# xmega1.net
KiCad netlist of a schematic drawn in EAGLE
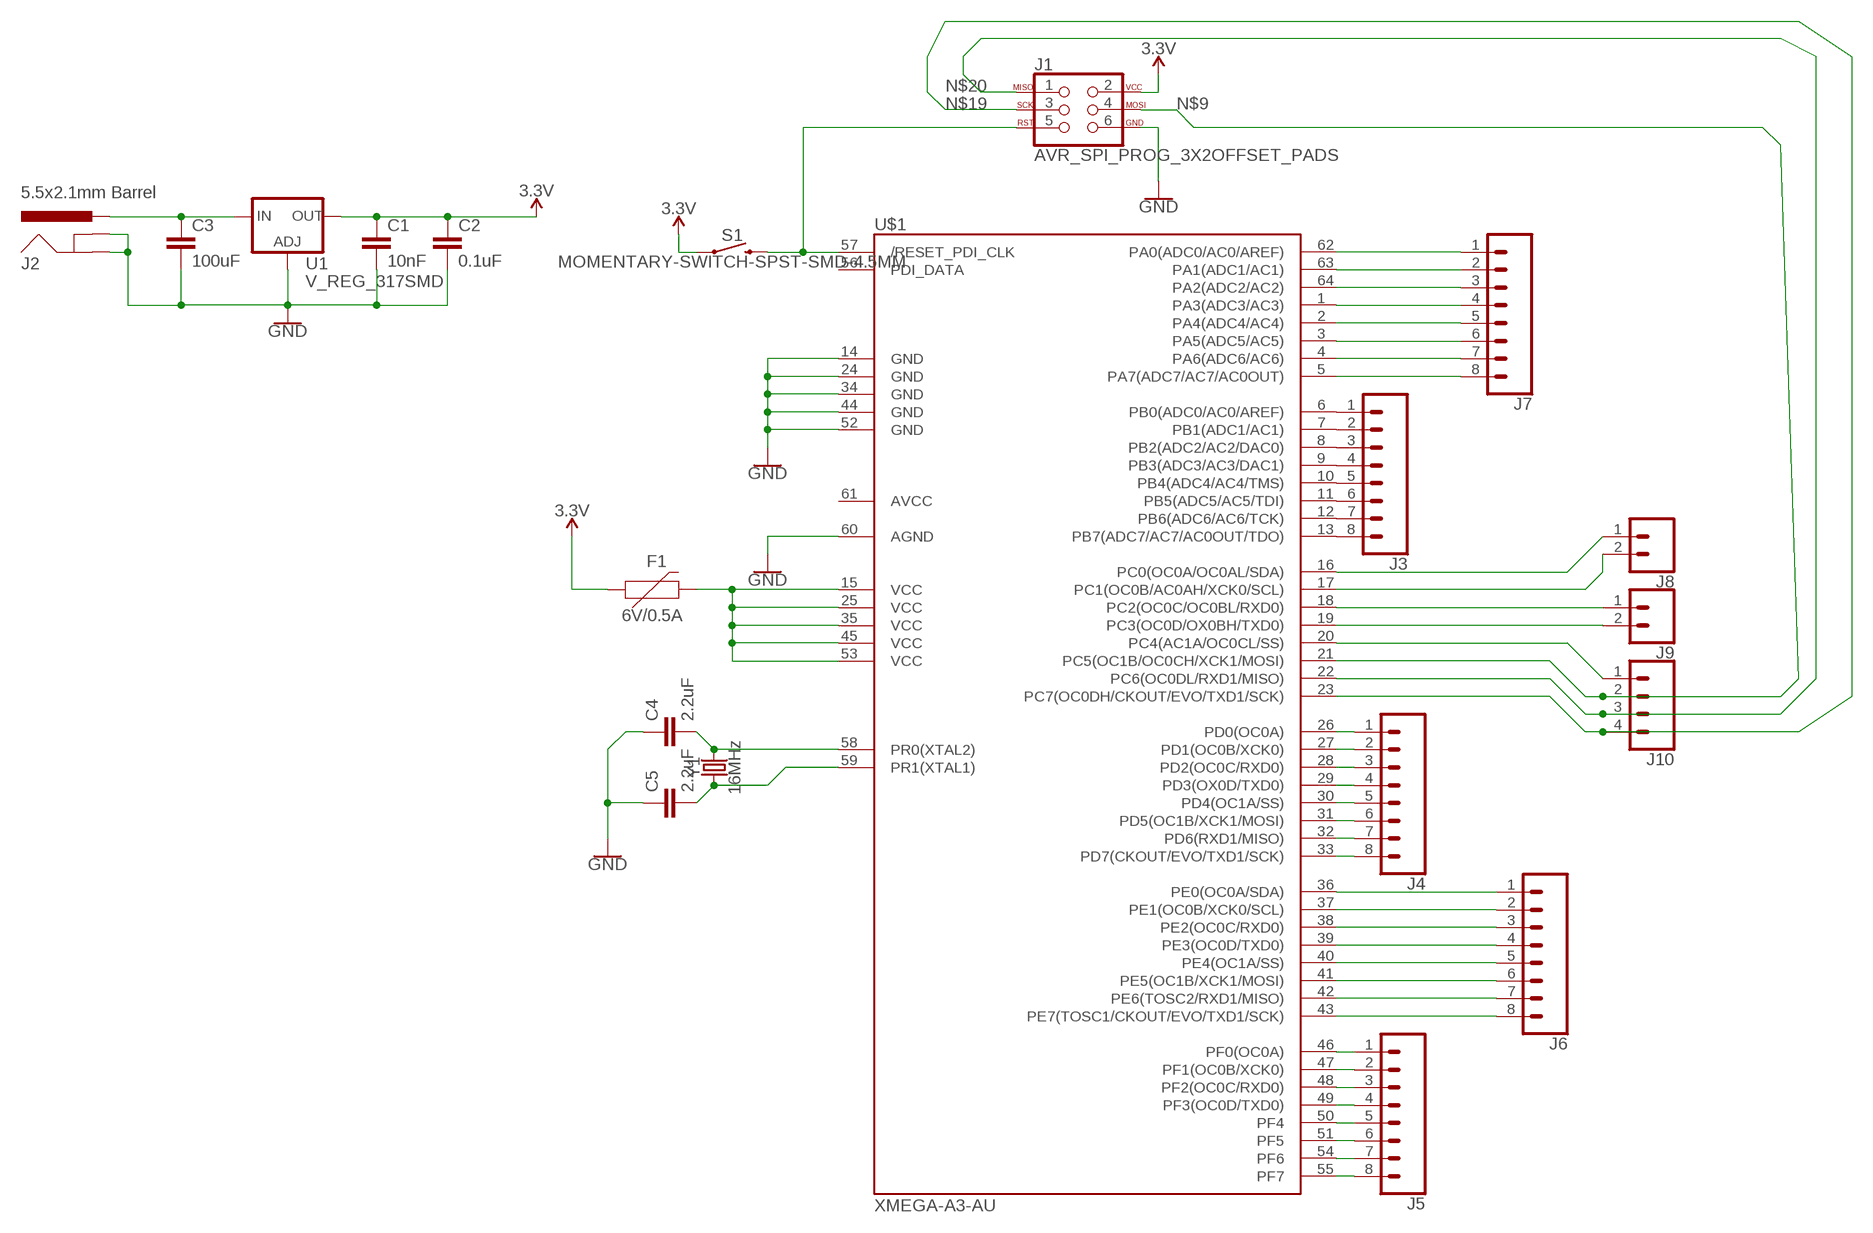
[diagram p0: schematic, sheet 1]

(export (version "E")
  (design (tool "Eeschema 10.0.6"))
  (components
    (comp (ref "C1")
      (value "10nF")
      (footprint "eagle-import:0603")
      (libsource (lib "eagle-import") (part "10NF-0603-50V-10%"))
    )
    (comp (ref "C2")
      (value "0.1uF")
      (footprint "eagle-import:0402-CAP")
      (libsource (lib "eagle-import") (part ".1UF-CER"))
    )
    (comp (ref "C3")
      (value "100uF")
      (footprint "eagle-import:1210")
      (libsource (lib "eagle-import") (part "100UF6.3V20%(1210)"))
    )
    (comp (ref "C4")
      (value "2.2uF")
      (footprint "eagle-import:0402-CAP")
      (libsource (lib "eagle-import") (part "2.2UF-CERCAP-07888"))
    )
    (comp (ref "C5")
      (value "2.2uF")
      (footprint "eagle-import:0402-CAP")
      (libsource (lib "eagle-import") (part "2.2UF-CERCAP-07888"))
    )
    (comp (ref "F1")
      (value "6V/0.5A")
      (footprint "eagle-import:1206")
      (libsource (lib "eagle-import") (part "PPTC_HALF-AMP"))
    )
    (comp (ref "J1")
      (value "AVR_SPI_PROG_3X2OFFSET_PADS")
      (footprint "eagle-import:2X3_OFFSET")
      (libsource (lib "eagle-import") (part "AVR_SPI_PROG_3X2OFFSET_PADS"))
    )
    (comp (ref "J2")
      (value "5.5x2.1mm Barrel")
      (footprint "eagle-import:POWER_JACK_SMD")
      (libsource (lib "eagle-import") (part "POWER_JACKSMD"))
    )
    (comp (ref "J3")
      (value "CONN_08LONGPADS")
      (footprint "eagle-import:1X08_LONGPADS")
      (libsource (lib "eagle-import") (part "CONN_08LONGPADS"))
    )
    (comp (ref "J4")
      (value "CONN_08LONGPADS")
      (footprint "eagle-import:1X08_LONGPADS")
      (libsource (lib "eagle-import") (part "CONN_08LONGPADS"))
    )
    (comp (ref "J5")
      (value "CONN_08LONGPADS")
      (footprint "eagle-import:1X08_LONGPADS")
      (libsource (lib "eagle-import") (part "CONN_08LONGPADS"))
    )
    (comp (ref "J6")
      (value "CONN_08LONGPADS")
      (footprint "eagle-import:1X08_LONGPADS")
      (libsource (lib "eagle-import") (part "CONN_08LONGPADS"))
    )
    (comp (ref "J7")
      (value "CONN_08LONGPADS")
      (footprint "eagle-import:1X08_LONGPADS")
      (libsource (lib "eagle-import") (part "CONN_08LONGPADS"))
    )
    (comp (ref "J8")
      (value "CONN_02PTH3")
      (footprint "eagle-import:1X02_LONGPADS")
      (libsource (lib "eagle-import") (part "CONN_02PTH3"))
    )
    (comp (ref "J9")
      (value "CONN_02PTH3")
      (footprint "eagle-import:1X02_LONGPADS")
      (libsource (lib "eagle-import") (part "CONN_02PTH3"))
    )
    (comp (ref "J10")
      (value "CONN_04LONGPADS")
      (footprint "eagle-import:1X04_LONGPADS")
      (libsource (lib "eagle-import") (part "CONN_04LONGPADS"))
    )
    (comp (ref "S1")
      (value "MOMENTARY-SWITCH-SPST-SMD-4.5MM")
      (footprint "eagle-import:TACTILE_SWITCH_SMD_4.5MM")
      (libsource (lib "eagle-import") (part "MOMENTARY-SWITCH-SPST-SMD-4.5MM"))
    )
    (comp (ref "U$1")
      (value "XMEGA-A3-AU")
      (footprint "eagle-import:TQFP64_14X14MM_MCU")
      (libsource (lib "eagle-import") (part "XMEGA-A3-AU"))
    )
    (comp (ref "U1")
      (value "V_REG_317SMD")
      (footprint "eagle-import:SOT223")
      (libsource (lib "eagle-import") (part "V_REG_317SMD"))
    )
    (comp (ref "Y1")
      (value "16MHz")
      (footprint "eagle-import:CRYSTAL-SMD-5X3.2-4PAD")
      (libsource (lib "eagle-import") (part "CRYSTAL-16MHZSMD-5X3.2"))
    )
  )
  (nets
    (net (code "1") (name "/N$9") (class "Default")
      (node (ref "J1") (pin "4") (pinfunction "4_4") (pintype "passive"))
      (node (ref "J10") (pin "2") (pinfunction "2_2") (pintype "passive"))
      (node (ref "U$1") (pin "21") (pinfunction "PC5(OC1B/OC0CH/XCK1/MOSI)_21") (pintype "bidirectional"))
    )
    (net (code "2") (name "/N$19") (class "Default")
      (node (ref "J1") (pin "3") (pinfunction "3_3") (pintype "passive"))
      (node (ref "J10") (pin "4") (pinfunction "4_4") (pintype "passive"))
      (node (ref "U$1") (pin "23") (pinfunction "PC7(OC0DH/CKOUT/EVO/TXD1/SCK)_23") (pintype "bidirectional"))
    )
    (net (code "3") (name "/N$20") (class "Default")
      (node (ref "J1") (pin "1") (pinfunction "1_1") (pintype "passive"))
      (node (ref "J10") (pin "3") (pinfunction "3_3") (pintype "passive"))
      (node (ref "U$1") (pin "22") (pinfunction "PC6(OC0DL/RXD1/MISO)_22") (pintype "bidirectional"))
    )
    (net (code "4") (name "3.3V") (class "Default")
      (node (ref "C1") (pin "1") (pinfunction "1_1") (pintype "passive"))
      (node (ref "C2") (pin "1") (pinfunction "1_1") (pintype "passive"))
      (node (ref "F1") (pin "1") (pinfunction "1_1") (pintype "bidirectional"))
      (node (ref "J1") (pin "2") (pinfunction "2_2") (pintype "passive"))
      (node (ref "S1") (pin "2") (pinfunction "1_2") (pintype "passive"))
      (node (ref "S1") (pin "3") (pinfunction "1_3") (pintype "passive"))
      (node (ref "U1") (pin "2") (pinfunction "OUT_2") (pintype "output"))
    )
    (net (code "5") (name "GND") (class "Default")
      (node (ref "C1") (pin "2") (pinfunction "2_2") (pintype "passive"))
      (node (ref "C2") (pin "2") (pinfunction "2_2") (pintype "passive"))
      (node (ref "C3") (pin "2") (pinfunction "2_2") (pintype "passive"))
      (node (ref "C4") (pin "1") (pinfunction "1_1") (pintype "passive"))
      (node (ref "C5") (pin "1") (pinfunction "1_1") (pintype "passive"))
      (node (ref "J1") (pin "6") (pinfunction "6_6") (pintype "passive"))
      (node (ref "J2") (pin "GND") (pinfunction "GNDBREAK_GND") (pintype "bidirectional"))
      (node (ref "J2") (pin "P$4") (pinfunction "GND_P$4") (pintype "bidirectional"))
      (node (ref "U$1") (pin "14") (pinfunction "GND1_14") (pintype "bidirectional"))
      (node (ref "U$1") (pin "24") (pinfunction "GND2_24") (pintype "bidirectional"))
      (node (ref "U$1") (pin "34") (pinfunction "GND3_34") (pintype "bidirectional"))
      (node (ref "U$1") (pin "44") (pinfunction "GND4_44") (pintype "bidirectional"))
      (node (ref "U$1") (pin "52") (pinfunction "GND5_52") (pintype "bidirectional"))
      (node (ref "U$1") (pin "60") (pinfunction "AGND_60") (pintype "bidirectional"))
      (node (ref "U1") (pin "1") (pinfunction "ADJ_1") (pintype "input"))
    )
    (net (code "6") (name "Net-(J2-PWR)") (class "Default")
      (node (ref "C3") (pin "1") (pinfunction "1_1") (pintype "passive"))
      (node (ref "J2") (pin "VIN0") (pinfunction "PWR_VIN0") (pintype "bidirectional"))
      (node (ref "U1") (pin "3") (pinfunction "IN_3") (pintype "input"))
    )
    (net (code "7") (name "Net-(U$1-PA0(ADC0{slash}AC0{slash}AREF))") (class "Default")
      (node (ref "J7") (pin "1") (pinfunction "1_1") (pintype "passive"))
      (node (ref "U$1") (pin "62") (pinfunction "PA0(ADC0/AC0/AREF)_62") (pintype "bidirectional"))
    )
    (net (code "8") (name "Net-(U$1-PA1(ADC1{slash}AC1))") (class "Default")
      (node (ref "J7") (pin "2") (pinfunction "2_2") (pintype "passive"))
      (node (ref "U$1") (pin "63") (pinfunction "PA1(ADC1/AC1)_63") (pintype "bidirectional"))
    )
    (net (code "9") (name "Net-(U$1-PA2(ADC2{slash}AC2))") (class "Default")
      (node (ref "J7") (pin "3") (pinfunction "3_3") (pintype "passive"))
      (node (ref "U$1") (pin "64") (pinfunction "PA2(ADC2/AC2)_64") (pintype "bidirectional"))
    )
    (net (code "10") (name "Net-(U$1-PA3(ADC3{slash}AC3))") (class "Default")
      (node (ref "J7") (pin "4") (pinfunction "4_4") (pintype "passive"))
      (node (ref "U$1") (pin "1") (pinfunction "PA3(ADC3/AC3)_1") (pintype "bidirectional"))
    )
    (net (code "11") (name "Net-(U$1-PA4(ADC4{slash}AC4))") (class "Default")
      (node (ref "J7") (pin "5") (pinfunction "5_5") (pintype "passive"))
      (node (ref "U$1") (pin "2") (pinfunction "PA4(ADC4/AC4)_2") (pintype "bidirectional"))
    )
    (net (code "12") (name "Net-(U$1-PA5(ADC5{slash}AC5))") (class "Default")
      (node (ref "J7") (pin "6") (pinfunction "6_6") (pintype "passive"))
      (node (ref "U$1") (pin "3") (pinfunction "PA5(ADC5/AC5)_3") (pintype "bidirectional"))
    )
    (net (code "13") (name "Net-(U$1-PA6(ADC6{slash}AC6))") (class "Default")
      (node (ref "J7") (pin "7") (pinfunction "7_7") (pintype "passive"))
      (node (ref "U$1") (pin "4") (pinfunction "PA6(ADC6/AC6)_4") (pintype "bidirectional"))
    )
    (net (code "14") (name "Net-(U$1-PA7(ADC7{slash}AC7{slash}AC0OUT))") (class "Default")
      (node (ref "J7") (pin "8") (pinfunction "8_8") (pintype "passive"))
      (node (ref "U$1") (pin "5") (pinfunction "PA7(ADC7/AC7/AC0OUT)_5") (pintype "bidirectional"))
    )
    (net (code "15") (name "Net-(U$1-PB0(ADC0{slash}AC0{slash}AREF))") (class "Default")
      (node (ref "J3") (pin "1") (pinfunction "1_1") (pintype "passive"))
      (node (ref "U$1") (pin "6") (pinfunction "PB0(ADC0/AC0/AREF)_6") (pintype "bidirectional"))
    )
    (net (code "16") (name "Net-(U$1-PB1(ADC1{slash}AC1))") (class "Default")
      (node (ref "J3") (pin "2") (pinfunction "2_2") (pintype "passive"))
      (node (ref "U$1") (pin "7") (pinfunction "PB1(ADC1/AC1)_7") (pintype "bidirectional"))
    )
    (net (code "17") (name "Net-(U$1-PB2(ADC2{slash}AC2{slash}DAC0))") (class "Default")
      (node (ref "J3") (pin "3") (pinfunction "3_3") (pintype "passive"))
      (node (ref "U$1") (pin "8") (pinfunction "PB2(ADC2/AC2/DAC0)_8") (pintype "bidirectional"))
    )
    (net (code "18") (name "Net-(U$1-PB3(ADC3{slash}AC3{slash}DAC1))") (class "Default")
      (node (ref "J3") (pin "4") (pinfunction "4_4") (pintype "passive"))
      (node (ref "U$1") (pin "9") (pinfunction "PB3(ADC3/AC3/DAC1)_9") (pintype "bidirectional"))
    )
    (net (code "19") (name "Net-(U$1-PB4(ADC4{slash}AC4{slash}TMS))") (class "Default")
      (node (ref "J3") (pin "5") (pinfunction "5_5") (pintype "passive"))
      (node (ref "U$1") (pin "10") (pinfunction "PB4(ADC4/AC4/TMS)_10") (pintype "bidirectional"))
    )
    (net (code "20") (name "Net-(U$1-PB5(ADC5{slash}AC5{slash}TDI))") (class "Default")
      (node (ref "J3") (pin "6") (pinfunction "6_6") (pintype "passive"))
      (node (ref "U$1") (pin "11") (pinfunction "PB5(ADC5/AC5/TDI)_11") (pintype "bidirectional"))
    )
    (net (code "21") (name "Net-(U$1-PB6(ADC6{slash}AC6{slash}TCK))") (class "Default")
      (node (ref "J3") (pin "7") (pinfunction "7_7") (pintype "passive"))
      (node (ref "U$1") (pin "12") (pinfunction "PB6(ADC6/AC6/TCK)_12") (pintype "bidirectional"))
    )
    (net (code "22") (name "Net-(U$1-PB7(ADC7{slash}AC7{slash}AC0OUT{slash}TDO))") (class "Default")
      (node (ref "J3") (pin "8") (pinfunction "8_8") (pintype "passive"))
      (node (ref "U$1") (pin "13") (pinfunction "PB7(ADC7/AC7/AC0OUT/TDO)_13") (pintype "bidirectional"))
    )
    (net (code "23") (name "Net-(U$1-PC0(OC0A{slash}OC0AL{slash}SDA))") (class "Default")
      (node (ref "J8") (pin "1") (pinfunction "1_1") (pintype "passive"))
      (node (ref "U$1") (pin "16") (pinfunction "PC0(OC0A/OC0AL/SDA)_16") (pintype "bidirectional"))
    )
    (net (code "24") (name "Net-(U$1-PC1(OC0B{slash}AC0AH{slash}XCK0{slash}SCL))") (class "Default")
      (node (ref "J8") (pin "2") (pinfunction "2_2") (pintype "passive"))
      (node (ref "U$1") (pin "17") (pinfunction "PC1(OC0B/AC0AH/XCK0/SCL)_17") (pintype "bidirectional"))
    )
    (net (code "25") (name "Net-(U$1-PC2(OC0C{slash}OC0BL{slash}RXD0))") (class "Default")
      (node (ref "J9") (pin "1") (pinfunction "1_1") (pintype "passive"))
      (node (ref "U$1") (pin "18") (pinfunction "PC2(OC0C/OC0BL/RXD0)_18") (pintype "bidirectional"))
    )
    (net (code "26") (name "Net-(U$1-PC3(OC0D{slash}OX0BH{slash}TXD0))") (class "Default")
      (node (ref "J9") (pin "2") (pinfunction "2_2") (pintype "passive"))
      (node (ref "U$1") (pin "19") (pinfunction "PC3(OC0D/OX0BH/TXD0)_19") (pintype "bidirectional"))
    )
    (net (code "27") (name "Net-(U$1-PC4(AC1A{slash}OC0CL{slash}SS))") (class "Default")
      (node (ref "J10") (pin "1") (pinfunction "1_1") (pintype "passive"))
      (node (ref "U$1") (pin "20") (pinfunction "PC4(AC1A/OC0CL/SS)_20") (pintype "bidirectional"))
    )
    (net (code "28") (name "Net-(U$1-PD0(OC0A))") (class "Default")
      (node (ref "J4") (pin "1") (pinfunction "1_1") (pintype "passive"))
      (node (ref "U$1") (pin "26") (pinfunction "PD0(OC0A)_26") (pintype "bidirectional"))
    )
    (net (code "29") (name "Net-(U$1-PD1(OC0B{slash}XCK0))") (class "Default")
      (node (ref "J4") (pin "2") (pinfunction "2_2") (pintype "passive"))
      (node (ref "U$1") (pin "27") (pinfunction "PD1(OC0B/XCK0)_27") (pintype "bidirectional"))
    )
    (net (code "30") (name "Net-(U$1-PD2(OC0C{slash}RXD0))") (class "Default")
      (node (ref "J4") (pin "3") (pinfunction "3_3") (pintype "passive"))
      (node (ref "U$1") (pin "28") (pinfunction "PD2(OC0C/RXD0)_28") (pintype "bidirectional"))
    )
    (net (code "31") (name "Net-(U$1-PD3(OX0D{slash}TXD0))") (class "Default")
      (node (ref "J4") (pin "4") (pinfunction "4_4") (pintype "passive"))
      (node (ref "U$1") (pin "29") (pinfunction "PD3(OX0D/TXD0)_29") (pintype "bidirectional"))
    )
    (net (code "32") (name "Net-(U$1-PD4(OC1A{slash}SS))") (class "Default")
      (node (ref "J4") (pin "5") (pinfunction "5_5") (pintype "passive"))
      (node (ref "U$1") (pin "30") (pinfunction "PD4(OC1A/SS)_30") (pintype "bidirectional"))
    )
    (net (code "33") (name "Net-(U$1-PD5(OC1B{slash}XCK1{slash}MOSI))") (class "Default")
      (node (ref "J4") (pin "6") (pinfunction "6_6") (pintype "passive"))
      (node (ref "U$1") (pin "31") (pinfunction "PD5(OC1B/XCK1/MOSI)_31") (pintype "bidirectional"))
    )
    (net (code "34") (name "Net-(U$1-PD6(RXD1{slash}MISO))") (class "Default")
      (node (ref "J4") (pin "7") (pinfunction "7_7") (pintype "passive"))
      (node (ref "U$1") (pin "32") (pinfunction "PD6(RXD1/MISO)_32") (pintype "bidirectional"))
    )
    (net (code "35") (name "Net-(U$1-PD7(CKOUT{slash}EVO{slash}TXD1{slash}SCK))") (class "Default")
      (node (ref "J4") (pin "8") (pinfunction "8_8") (pintype "passive"))
      (node (ref "U$1") (pin "33") (pinfunction "PD7(CKOUT/EVO/TXD1/SCK)_33") (pintype "bidirectional"))
    )
    (net (code "36") (name "Net-(U$1-PE0(OC0A{slash}SDA))") (class "Default")
      (node (ref "J6") (pin "1") (pinfunction "1_1") (pintype "passive"))
      (node (ref "U$1") (pin "36") (pinfunction "PE0(OC0A/SDA)_36") (pintype "bidirectional"))
    )
    (net (code "37") (name "Net-(U$1-PE1(OC0B{slash}XCK0{slash}SCL))") (class "Default")
      (node (ref "J6") (pin "2") (pinfunction "2_2") (pintype "passive"))
      (node (ref "U$1") (pin "37") (pinfunction "PE1(OC0B/XCK0/SCL)_37") (pintype "bidirectional"))
    )
    (net (code "38") (name "Net-(U$1-PE2(OC0C{slash}RXD0))") (class "Default")
      (node (ref "J6") (pin "3") (pinfunction "3_3") (pintype "passive"))
      (node (ref "U$1") (pin "38") (pinfunction "PE2(OC0C/RXD0)_38") (pintype "bidirectional"))
    )
    (net (code "39") (name "Net-(U$1-PE3(OC0D{slash}TXD0))") (class "Default")
      (node (ref "J6") (pin "4") (pinfunction "4_4") (pintype "passive"))
      (node (ref "U$1") (pin "39") (pinfunction "PE3(OC0D/TXD0)_39") (pintype "bidirectional"))
    )
    (net (code "40") (name "Net-(U$1-PE4(OC1A{slash}SS))") (class "Default")
      (node (ref "J6") (pin "5") (pinfunction "5_5") (pintype "passive"))
      (node (ref "U$1") (pin "40") (pinfunction "PE4(OC1A/SS)_40") (pintype "bidirectional"))
    )
    (net (code "41") (name "Net-(U$1-PE5(OC1B{slash}XCK1{slash}MOSI))") (class "Default")
      (node (ref "J6") (pin "6") (pinfunction "6_6") (pintype "passive"))
      (node (ref "U$1") (pin "41") (pinfunction "PE5(OC1B/XCK1/MOSI)_41") (pintype "bidirectional"))
    )
    (net (code "42") (name "Net-(U$1-PE6(TOSC2{slash}RXD1{slash}MISO))") (class "Default")
      (node (ref "J6") (pin "7") (pinfunction "7_7") (pintype "passive"))
      (node (ref "U$1") (pin "42") (pinfunction "PE6(TOSC2/RXD1/MISO)_42") (pintype "bidirectional"))
    )
    (net (code "43") (name "Net-(U$1-PE7(TOSC1{slash}CKOUT{slash}EVO{slash}TXD1{slash}SCK))") (class "Default")
      (node (ref "J6") (pin "8") (pinfunction "8_8") (pintype "passive"))
      (node (ref "U$1") (pin "43") (pinfunction "PE7(TOSC1/CKOUT/EVO/TXD1/SCK)_43") (pintype "bidirectional"))
    )
    (net (code "44") (name "Net-(U$1-PF0(OC0A))") (class "Default")
      (node (ref "J5") (pin "1") (pinfunction "1_1") (pintype "passive"))
      (node (ref "U$1") (pin "46") (pinfunction "PF0(OC0A)_46") (pintype "bidirectional"))
    )
    (net (code "45") (name "Net-(U$1-PF1(OC0B{slash}XCK0))") (class "Default")
      (node (ref "J5") (pin "2") (pinfunction "2_2") (pintype "passive"))
      (node (ref "U$1") (pin "47") (pinfunction "PF1(OC0B/XCK0)_47") (pintype "bidirectional"))
    )
    (net (code "46") (name "Net-(U$1-PF2(OC0C{slash}RXD0))") (class "Default")
      (node (ref "J5") (pin "3") (pinfunction "3_3") (pintype "passive"))
      (node (ref "U$1") (pin "48") (pinfunction "PF2(OC0C/RXD0)_48") (pintype "bidirectional"))
    )
    (net (code "47") (name "Net-(U$1-PF3(OC0D{slash}TXD0))") (class "Default")
      (node (ref "J5") (pin "4") (pinfunction "4_4") (pintype "passive"))
      (node (ref "U$1") (pin "49") (pinfunction "PF3(OC0D/TXD0)_49") (pintype "bidirectional"))
    )
    (net (code "48") (name "Net-(U$1-PF4)") (class "Default")
      (node (ref "J5") (pin "5") (pinfunction "5_5") (pintype "passive"))
      (node (ref "U$1") (pin "50") (pinfunction "PF4_50") (pintype "bidirectional"))
    )
    (net (code "49") (name "Net-(U$1-PF5)") (class "Default")
      (node (ref "J5") (pin "6") (pinfunction "6_6") (pintype "passive"))
      (node (ref "U$1") (pin "51") (pinfunction "PF5_51") (pintype "bidirectional"))
    )
    (net (code "50") (name "Net-(U$1-PF6)") (class "Default")
      (node (ref "J5") (pin "7") (pinfunction "7_7") (pintype "passive"))
      (node (ref "U$1") (pin "54") (pinfunction "PF6_54") (pintype "bidirectional"))
    )
    (net (code "51") (name "Net-(U$1-PF7)") (class "Default")
      (node (ref "J5") (pin "8") (pinfunction "8_8") (pintype "passive"))
      (node (ref "U$1") (pin "55") (pinfunction "PF7_55") (pintype "bidirectional"))
    )
    (net (code "52") (name "Net-(U$1-PR0(XTAL2))") (class "Default")
      (node (ref "C4") (pin "2") (pinfunction "2_2") (pintype "passive"))
      (node (ref "U$1") (pin "58") (pinfunction "PR0(XTAL2)_58") (pintype "bidirectional"))
      (node (ref "Y1") (pin "3") (pinfunction "2_3") (pintype "passive"))
    )
    (net (code "53") (name "Net-(U$1-PR1(XTAL1))") (class "Default")
      (node (ref "C5") (pin "2") (pinfunction "2_2") (pintype "passive"))
      (node (ref "U$1") (pin "59") (pinfunction "PR1(XTAL1)_59") (pintype "bidirectional"))
      (node (ref "Y1") (pin "1") (pinfunction "1_1") (pintype "passive"))
    )
    (net (code "54") (name "Net-(U$1-VCC1)") (class "Default")
      (node (ref "F1") (pin "2") (pinfunction "2_2") (pintype "bidirectional"))
      (node (ref "U$1") (pin "15") (pinfunction "VCC1_15") (pintype "bidirectional"))
      (node (ref "U$1") (pin "25") (pinfunction "VCC2_25") (pintype "bidirectional"))
      (node (ref "U$1") (pin "35") (pinfunction "VCC3_35") (pintype "bidirectional"))
      (node (ref "U$1") (pin "45") (pinfunction "VCC4_45") (pintype "bidirectional"))
      (node (ref "U$1") (pin "53") (pinfunction "VCC5_53") (pintype "bidirectional"))
    )
    (net (code "55") (name "Net-(U$1-{slash}RESET_PDI_CLK)") (class "Default")
      (node (ref "J1") (pin "5") (pinfunction "5_5") (pintype "passive"))
      (node (ref "S1") (pin "1") (pinfunction "2_1") (pintype "passive"))
      (node (ref "S1") (pin "4") (pinfunction "2_4") (pintype "passive"))
      (node (ref "U$1") (pin "57") (pinfunction "/RESET_PDI_CLK_57") (pintype "bidirectional"))
    )
    (net (code "56") (name "unconnected-(U$1-AVCC-Pad61)") (class "Default")
      (node (ref "U$1") (pin "61") (pinfunction "AVCC_61") (pintype "bidirectional"))
    )
    (net (code "57") (name "unconnected-(U$1-PDI_DATA-Pad56)") (class "Default")
      (node (ref "U$1") (pin "56") (pinfunction "PDI_DATA_56") (pintype "bidirectional"))
    )
  )
)
